# Pressure_sensors.net
KiCad netlist of a schematic drawn in Altium Designer
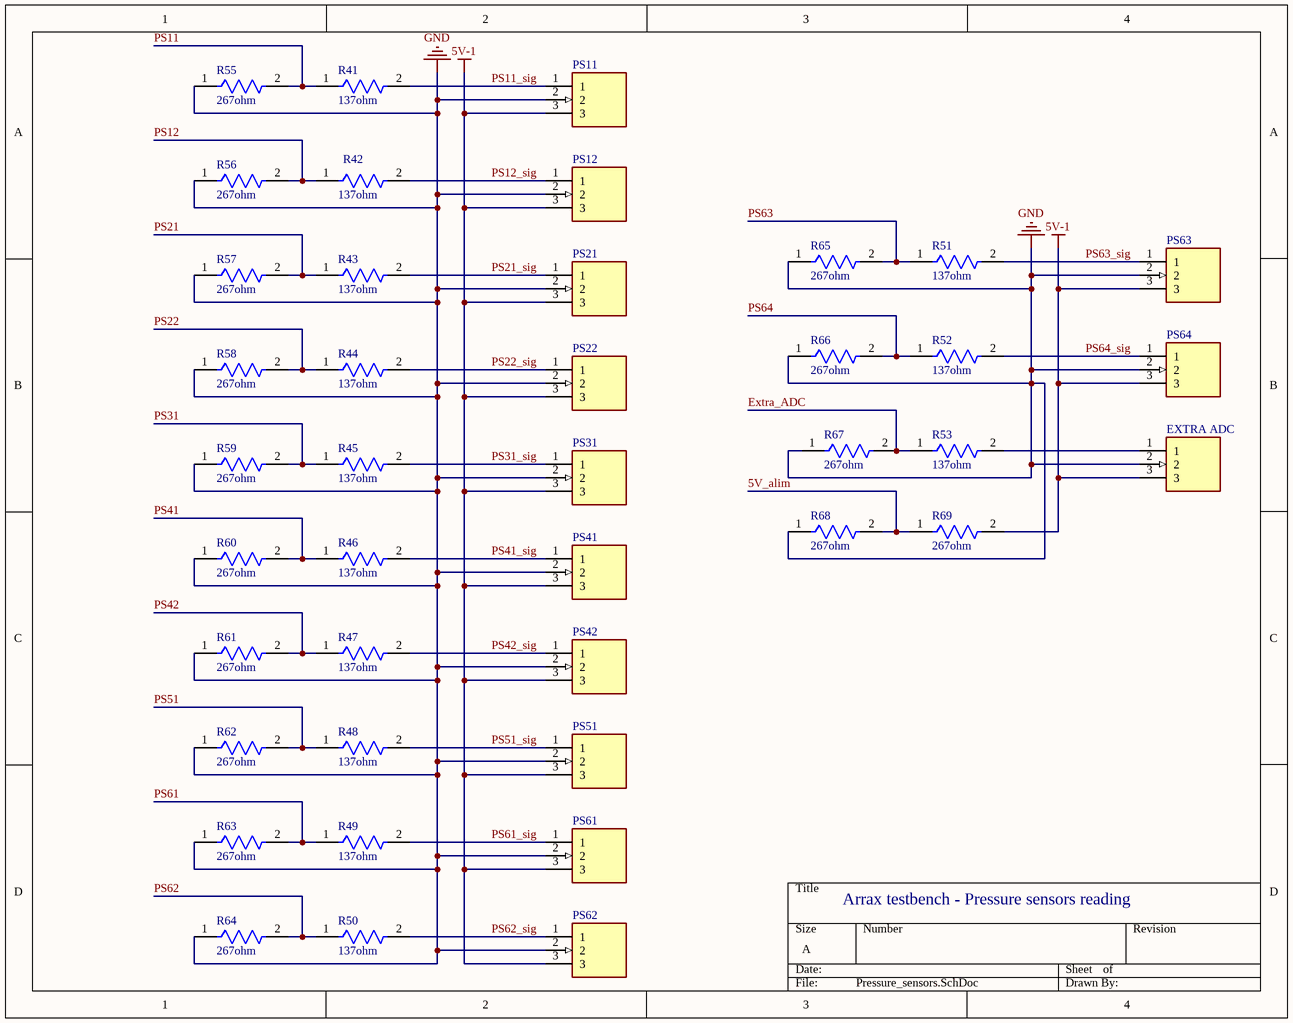
[diagram p0: Pressure_sensors.SchDoc]

(export (version "E")
  (design (tool "Eeschema 10.0.6"))
  (components
    (comp (ref "EXTRA ADC")
      (value "640456-3")
      (footprint "SamacSys:HDRV3W107P0X254_1X3_762X572X1080P")
      (description "Connector")
      (fields (field (name "MOUSER PART NUMBER") "571-6404563"))
      (libsource (lib "*") (part "640456-3"))
    )
    (comp (ref "PS11")
      (value "640456-3")
      (footprint "SamacSys:HDRV3W107P0X254_1X3_762X572X1080P")
      (description "Connector")
      (fields (field (name "MOUSER PART NUMBER") "571-6404563"))
      (libsource (lib "*") (part "640456-3"))
    )
    (comp (ref "PS12")
      (value "640456-3")
      (footprint "SamacSys:HDRV3W107P0X254_1X3_762X572X1080P")
      (description "Connector")
      (fields (field (name "MOUSER PART NUMBER") "571-6404563"))
      (libsource (lib "*") (part "640456-3"))
    )
    (comp (ref "PS21")
      (value "640456-3")
      (footprint "SamacSys:HDRV3W107P0X254_1X3_762X572X1080P")
      (description "Connector")
      (fields (field (name "MOUSER PART NUMBER") "571-6404563"))
      (libsource (lib "*") (part "640456-3"))
    )
    (comp (ref "PS22")
      (value "640456-3")
      (footprint "SamacSys:HDRV3W107P0X254_1X3_762X572X1080P")
      (description "Connector")
      (fields (field (name "MOUSER PART NUMBER") "571-6404563"))
      (libsource (lib "*") (part "640456-3"))
    )
    (comp (ref "PS31")
      (value "640456-3")
      (footprint "SamacSys:HDRV3W107P0X254_1X3_762X572X1080P")
      (description "Connector")
      (fields (field (name "MOUSER PART NUMBER") "571-6404563"))
      (libsource (lib "*") (part "640456-3"))
    )
    (comp (ref "PS41")
      (value "640456-3")
      (footprint "SamacSys:HDRV3W107P0X254_1X3_762X572X1080P")
      (description "Connector")
      (fields (field (name "MOUSER PART NUMBER") "571-6404563"))
      (libsource (lib "*") (part "640456-3"))
    )
    (comp (ref "PS42")
      (value "640456-3")
      (footprint "SamacSys:HDRV3W107P0X254_1X3_762X572X1080P")
      (description "Connector")
      (fields (field (name "MOUSER PART NUMBER") "571-6404563"))
      (libsource (lib "*") (part "640456-3"))
    )
    (comp (ref "PS51")
      (value "640456-3")
      (footprint "SamacSys:HDRV3W107P0X254_1X3_762X572X1080P")
      (description "Connector")
      (fields (field (name "MOUSER PART NUMBER") "571-6404563"))
      (libsource (lib "*") (part "640456-3"))
    )
    (comp (ref "PS61")
      (value "640456-3")
      (footprint "SamacSys:HDRV3W107P0X254_1X3_762X572X1080P")
      (description "Connector")
      (fields (field (name "MOUSER PART NUMBER") "571-6404563"))
      (libsource (lib "*") (part "640456-3"))
    )
    (comp (ref "PS62")
      (value "640456-3")
      (footprint "SamacSys:HDRV3W107P0X254_1X3_762X572X1080P")
      (description "Connector")
      (fields (field (name "MOUSER PART NUMBER") "571-6404563"))
      (libsource (lib "*") (part "640456-3"))
    )
    (comp (ref "PS63")
      (value "640456-3")
      (footprint "SamacSys:HDRV3W107P0X254_1X3_762X572X1080P")
      (description "Connector")
      (fields (field (name "MOUSER PART NUMBER") "571-6404563"))
      (libsource (lib "*") (part "640456-3"))
    )
    (comp (ref "PS64")
      (value "640456-3")
      (footprint "SamacSys:HDRV3W107P0X254_1X3_762X572X1080P")
      (description "Connector")
      (fields (field (name "MOUSER PART NUMBER") "571-6404563"))
      (libsource (lib "*") (part "640456-3"))
    )
    (comp (ref "R41")
      (value "137ohm")
      (footprint "FP-RP73P-2A-MFG")
      (description "RP73P 0805 137Ω 0.25W 25ppm/°C 0.10% 150V")
      (fields
        (field (name "MANUFACTURER PART NUMBER") "RP73PF2A137RBTDF")
        (field (name "MANUFACTURER") "TE Connectivity")
      )
      (libsource (lib "Altium Content Vault") (part "1029c3af85768c4190bb7ad29bc67b5"))
    )
    (comp (ref "R42")
      (value "137ohm")
      (footprint "FP-RP73P-2A-MFG")
      (description "RP73P 0805 137Ω 0.25W 25ppm/°C 0.10% 150V")
      (fields
        (field (name "MANUFACTURER PART NUMBER") "RP73PF2A137RBTDF")
        (field (name "MANUFACTURER") "TE Connectivity")
      )
      (libsource (lib "Altium Content Vault") (part "1029c3af85768c4190bb7ad29bc67b5"))
    )
    (comp (ref "R43")
      (value "137ohm")
      (footprint "FP-RP73P-2A-MFG")
      (description "RP73P 0805 137Ω 0.25W 25ppm/°C 0.10% 150V")
      (fields
        (field (name "MANUFACTURER PART NUMBER") "RP73PF2A137RBTDF")
        (field (name "MANUFACTURER") "TE Connectivity")
      )
      (libsource (lib "Altium Content Vault") (part "1029c3af85768c4190bb7ad29bc67b5"))
    )
    (comp (ref "R44")
      (value "137ohm")
      (footprint "FP-RP73P-2A-MFG")
      (description "RP73P 0805 137Ω 0.25W 25ppm/°C 0.10% 150V")
      (fields
        (field (name "MANUFACTURER PART NUMBER") "RP73PF2A137RBTDF")
        (field (name "MANUFACTURER") "TE Connectivity")
      )
      (libsource (lib "Altium Content Vault") (part "1029c3af85768c4190bb7ad29bc67b5"))
    )
    (comp (ref "R45")
      (value "137ohm")
      (footprint "FP-RP73P-2A-MFG")
      (description "RP73P 0805 137Ω 0.25W 25ppm/°C 0.10% 150V")
      (fields
        (field (name "MANUFACTURER PART NUMBER") "RP73PF2A137RBTDF")
        (field (name "MANUFACTURER") "TE Connectivity")
      )
      (libsource (lib "Altium Content Vault") (part "1029c3af85768c4190bb7ad29bc67b5"))
    )
    (comp (ref "R46")
      (value "137ohm")
      (footprint "FP-RP73P-2A-MFG")
      (description "RP73P 0805 137Ω 0.25W 25ppm/°C 0.10% 150V")
      (fields
        (field (name "MANUFACTURER PART NUMBER") "RP73PF2A137RBTDF")
        (field (name "MANUFACTURER") "TE Connectivity")
      )
      (libsource (lib "Altium Content Vault") (part "1029c3af85768c4190bb7ad29bc67b5"))
    )
    (comp (ref "R47")
      (value "137ohm")
      (footprint "FP-RP73P-2A-MFG")
      (description "RP73P 0805 137Ω 0.25W 25ppm/°C 0.10% 150V")
      (fields
        (field (name "MANUFACTURER PART NUMBER") "RP73PF2A137RBTDF")
        (field (name "MANUFACTURER") "TE Connectivity")
      )
      (libsource (lib "Altium Content Vault") (part "1029c3af85768c4190bb7ad29bc67b5"))
    )
    (comp (ref "R48")
      (value "137ohm")
      (footprint "FP-RP73P-2A-MFG")
      (description "RP73P 0805 137Ω 0.25W 25ppm/°C 0.10% 150V")
      (fields
        (field (name "MANUFACTURER PART NUMBER") "RP73PF2A137RBTDF")
        (field (name "MANUFACTURER") "TE Connectivity")
      )
      (libsource (lib "Altium Content Vault") (part "1029c3af85768c4190bb7ad29bc67b5"))
    )
    (comp (ref "R49")
      (value "137ohm")
      (footprint "FP-RP73P-2A-MFG")
      (description "RP73P 0805 137Ω 0.25W 25ppm/°C 0.10% 150V")
      (fields
        (field (name "MANUFACTURER PART NUMBER") "RP73PF2A137RBTDF")
        (field (name "MANUFACTURER") "TE Connectivity")
      )
      (libsource (lib "Altium Content Vault") (part "1029c3af85768c4190bb7ad29bc67b5"))
    )
    (comp (ref "R50")
      (value "137ohm")
      (footprint "FP-RP73P-2A-MFG")
      (description "RP73P 0805 137Ω 0.25W 25ppm/°C 0.10% 150V")
      (fields
        (field (name "MANUFACTURER PART NUMBER") "RP73PF2A137RBTDF")
        (field (name "MANUFACTURER") "TE Connectivity")
      )
      (libsource (lib "Altium Content Vault") (part "1029c3af85768c4190bb7ad29bc67b5"))
    )
    (comp (ref "R51")
      (value "137ohm")
      (footprint "FP-RP73P-2A-MFG")
      (description "RP73P 0805 137Ω 0.25W 25ppm/°C 0.10% 150V")
      (fields
        (field (name "MANUFACTURER PART NUMBER") "RP73PF2A137RBTDF")
        (field (name "MANUFACTURER") "TE Connectivity")
      )
      (libsource (lib "Altium Content Vault") (part "1029c3af85768c4190bb7ad29bc67b5"))
    )
    (comp (ref "R52")
      (value "137ohm")
      (footprint "FP-RP73P-2A-MFG")
      (description "RP73P 0805 137Ω 0.25W 25ppm/°C 0.10% 150V")
      (fields
        (field (name "MANUFACTURER PART NUMBER") "RP73PF2A137RBTDF")
        (field (name "MANUFACTURER") "TE Connectivity")
      )
      (libsource (lib "Altium Content Vault") (part "1029c3af85768c4190bb7ad29bc67b5"))
    )
    (comp (ref "R53")
      (value "137ohm")
      (footprint "FP-RP73P-2A-MFG")
      (description "RP73P 0805 137Ω 0.25W 25ppm/°C 0.10% 150V")
      (fields
        (field (name "MANUFACTURER PART NUMBER") "RP73PF2A137RBTDF")
        (field (name "MANUFACTURER") "TE Connectivity")
      )
      (libsource (lib "Altium Content Vault") (part "1029c3af85768c4190bb7ad29bc67b5"))
    )
    (comp (ref "R55")
      (value "267ohm")
      (footprint "FP-RP73P-2A-MFG")
      (description "RP73P 0805 267Ω 0.25W 25ppm/°C 0.10% 150V")
      (fields (field (name "TOLERANCE") "0.001") (field (name "MANUFACTURER PART NUMBER") "RP73PF2A267RBTDF"))
      (libsource (lib "Altium Content Vault") (part "1029c3af85768c4190bb7ad29bc67b5"))
    )
    (comp (ref "R56")
      (value "267ohm")
      (footprint "FP-RP73P-2A-MFG")
      (description "RP73P 0805 267Ω 0.25W 25ppm/°C 0.10% 150V")
      (fields (field (name "TOLERANCE") "0.001") (field (name "MANUFACTURER PART NUMBER") "RP73PF2A267RBTDF"))
      (libsource (lib "Altium Content Vault") (part "1029c3af85768c4190bb7ad29bc67b5"))
    )
    (comp (ref "R57")
      (value "267ohm")
      (footprint "FP-RP73P-2A-MFG")
      (description "RP73P 0805 267Ω 0.25W 25ppm/°C 0.10% 150V")
      (fields (field (name "TOLERANCE") "0.001") (field (name "MANUFACTURER PART NUMBER") "RP73PF2A267RBTDF"))
      (libsource (lib "Altium Content Vault") (part "1029c3af85768c4190bb7ad29bc67b5"))
    )
    (comp (ref "R58")
      (value "267ohm")
      (footprint "FP-RP73P-2A-MFG")
      (description "RP73P 0805 267Ω 0.25W 25ppm/°C 0.10% 150V")
      (fields (field (name "TOLERANCE") "0.001") (field (name "MANUFACTURER PART NUMBER") "RP73PF2A267RBTDF"))
      (libsource (lib "Altium Content Vault") (part "1029c3af85768c4190bb7ad29bc67b5"))
    )
    (comp (ref "R59")
      (value "267ohm")
      (footprint "FP-RP73P-2A-MFG")
      (description "RP73P 0805 267Ω 0.25W 25ppm/°C 0.10% 150V")
      (fields (field (name "TOLERANCE") "0.001") (field (name "MANUFACTURER PART NUMBER") "RP73PF2A267RBTDF"))
      (libsource (lib "Altium Content Vault") (part "1029c3af85768c4190bb7ad29bc67b5"))
    )
    (comp (ref "R60")
      (value "267ohm")
      (footprint "FP-RP73P-2A-MFG")
      (description "RP73P 0805 267Ω 0.25W 25ppm/°C 0.10% 150V")
      (fields (field (name "TOLERANCE") "0.001") (field (name "MANUFACTURER PART NUMBER") "RP73PF2A267RBTDF"))
      (libsource (lib "Altium Content Vault") (part "1029c3af85768c4190bb7ad29bc67b5"))
    )
    (comp (ref "R61")
      (value "267ohm")
      (footprint "FP-RP73P-2A-MFG")
      (description "RP73P 0805 267Ω 0.25W 25ppm/°C 0.10% 150V")
      (fields (field (name "TOLERANCE") "0.001") (field (name "MANUFACTURER PART NUMBER") "RP73PF2A267RBTDF"))
      (libsource (lib "Altium Content Vault") (part "1029c3af85768c4190bb7ad29bc67b5"))
    )
    (comp (ref "R62")
      (value "267ohm")
      (footprint "FP-RP73P-2A-MFG")
      (description "RP73P 0805 267Ω 0.25W 25ppm/°C 0.10% 150V")
      (fields (field (name "TOLERANCE") "0.001") (field (name "MANUFACTURER PART NUMBER") "RP73PF2A267RBTDF"))
      (libsource (lib "Altium Content Vault") (part "1029c3af85768c4190bb7ad29bc67b5"))
    )
    (comp (ref "R63")
      (value "267ohm")
      (footprint "FP-RP73P-2A-MFG")
      (description "RP73P 0805 267Ω 0.25W 25ppm/°C 0.10% 150V")
      (fields (field (name "TOLERANCE") "0.001") (field (name "MANUFACTURER PART NUMBER") "RP73PF2A267RBTDF"))
      (libsource (lib "Altium Content Vault") (part "1029c3af85768c4190bb7ad29bc67b5"))
    )
    (comp (ref "R64")
      (value "267ohm")
      (footprint "FP-RP73P-2A-MFG")
      (description "RP73P 0805 267Ω 0.25W 25ppm/°C 0.10% 150V")
      (fields (field (name "TOLERANCE") "0.001") (field (name "MANUFACTURER PART NUMBER") "RP73PF2A267RBTDF"))
      (libsource (lib "Altium Content Vault") (part "1029c3af85768c4190bb7ad29bc67b5"))
    )
    (comp (ref "R65")
      (value "267ohm")
      (footprint "FP-RP73P-2A-MFG")
      (description "RP73P 0805 267Ω 0.25W 25ppm/°C 0.10% 150V")
      (fields (field (name "TOLERANCE") "0.001") (field (name "MANUFACTURER PART NUMBER") "RP73PF2A267RBTDF"))
      (libsource (lib "Altium Content Vault") (part "1029c3af85768c4190bb7ad29bc67b5"))
    )
    (comp (ref "R66")
      (value "267ohm")
      (footprint "FP-RP73P-2A-MFG")
      (description "RP73P 0805 267Ω 0.25W 25ppm/°C 0.10% 150V")
      (fields (field (name "TOLERANCE") "0.001") (field (name "MANUFACTURER PART NUMBER") "RP73PF2A267RBTDF"))
      (libsource (lib "Altium Content Vault") (part "1029c3af85768c4190bb7ad29bc67b5"))
    )
    (comp (ref "R67")
      (value "267ohm")
      (footprint "FP-RP73P-2A-MFG")
      (description "RP73P 0805 267Ω 0.25W 25ppm/°C 0.10% 150V")
      (fields (field (name "TOLERANCE") "0.001") (field (name "MANUFACTURER PART NUMBER") "RP73PF2A267RBTDF"))
      (libsource (lib "Altium Content Vault") (part "1029c3af85768c4190bb7ad29bc67b5"))
    )
    (comp (ref "R68")
      (value "267ohm")
      (footprint "FP-RP73P-2A-MFG")
      (description "RP73P 0805 267Ω 0.25W 25ppm/°C 0.10% 150V")
      (fields (field (name "TOLERANCE") "0.001") (field (name "MANUFACTURER PART NUMBER") "RP73PF2A267RBTDF"))
      (libsource (lib "Altium Content Vault") (part "1029c3af85768c4190bb7ad29bc67b5"))
    )
    (comp (ref "R69")
      (value "267ohm")
      (footprint "FP-RP73P-2A-MFG")
      (description "RP73P 0805 267Ω 0.25W 25ppm/°C 0.10% 150V")
      (fields (field (name "TOLERANCE") "0.001") (field (name "MANUFACTURER PART NUMBER") "RP73PF2A267RBTDF"))
      (libsource (lib "Altium Content Vault") (part "1029c3af85768c4190bb7ad29bc67b5"))
    )
  )
  (nets
    (net (code "1") (name "/5V_alim") (class "Default")
      (node (ref "R68") (pin "2") (pinfunction "2_2") (pintype "passive"))
      (node (ref "R69") (pin "1") (pinfunction "1_1") (pintype "passive"))
    )
    (net (code "2") (name "/Extra_ADC") (class "Default")
      (node (ref "R53") (pin "1") (pinfunction "1_1") (pintype "passive"))
      (node (ref "R67") (pin "2") (pinfunction "2_2") (pintype "passive"))
    )
    (net (code "3") (name "/PS11") (class "Default")
      (node (ref "R41") (pin "1") (pinfunction "1_1") (pintype "passive"))
      (node (ref "R55") (pin "2") (pinfunction "2_2") (pintype "passive"))
    )
    (net (code "4") (name "/PS11_sig") (class "Default")
      (node (ref "PS11") (pin "1") (pinfunction "1_1") (pintype "passive"))
      (node (ref "R41") (pin "2") (pinfunction "2_2") (pintype "passive"))
    )
    (net (code "5") (name "/PS12") (class "Default")
      (node (ref "R42") (pin "1") (pinfunction "1_1") (pintype "passive"))
      (node (ref "R56") (pin "2") (pinfunction "2_2") (pintype "passive"))
    )
    (net (code "6") (name "/PS12_sig") (class "Default")
      (node (ref "PS12") (pin "1") (pinfunction "1_1") (pintype "passive"))
      (node (ref "R42") (pin "2") (pinfunction "2_2") (pintype "passive"))
    )
    (net (code "7") (name "/PS21") (class "Default")
      (node (ref "R43") (pin "1") (pinfunction "1_1") (pintype "passive"))
      (node (ref "R57") (pin "2") (pinfunction "2_2") (pintype "passive"))
    )
    (net (code "8") (name "/PS21_sig") (class "Default")
      (node (ref "PS21") (pin "1") (pinfunction "1_1") (pintype "passive"))
      (node (ref "R43") (pin "2") (pinfunction "2_2") (pintype "passive"))
    )
    (net (code "9") (name "/PS22") (class "Default")
      (node (ref "R44") (pin "1") (pinfunction "1_1") (pintype "passive"))
      (node (ref "R58") (pin "2") (pinfunction "2_2") (pintype "passive"))
    )
    (net (code "10") (name "/PS22_sig") (class "Default")
      (node (ref "PS22") (pin "1") (pinfunction "1_1") (pintype "passive"))
      (node (ref "R44") (pin "2") (pinfunction "2_2") (pintype "passive"))
    )
    (net (code "11") (name "/PS31") (class "Default")
      (node (ref "R45") (pin "1") (pinfunction "1_1") (pintype "passive"))
      (node (ref "R59") (pin "2") (pinfunction "2_2") (pintype "passive"))
    )
    (net (code "12") (name "/PS31_sig") (class "Default")
      (node (ref "PS31") (pin "1") (pinfunction "1_1") (pintype "passive"))
      (node (ref "R45") (pin "2") (pinfunction "2_2") (pintype "passive"))
    )
    (net (code "13") (name "/PS41") (class "Default")
      (node (ref "R46") (pin "1") (pinfunction "1_1") (pintype "passive"))
      (node (ref "R60") (pin "2") (pinfunction "2_2") (pintype "passive"))
    )
    (net (code "14") (name "/PS41_sig") (class "Default")
      (node (ref "PS41") (pin "1") (pinfunction "1_1") (pintype "passive"))
      (node (ref "R46") (pin "2") (pinfunction "2_2") (pintype "passive"))
    )
    (net (code "15") (name "/PS42") (class "Default")
      (node (ref "R47") (pin "1") (pinfunction "1_1") (pintype "passive"))
      (node (ref "R61") (pin "2") (pinfunction "2_2") (pintype "passive"))
    )
    (net (code "16") (name "/PS42_sig") (class "Default")
      (node (ref "PS42") (pin "1") (pinfunction "1_1") (pintype "passive"))
      (node (ref "R47") (pin "2") (pinfunction "2_2") (pintype "passive"))
    )
    (net (code "17") (name "/PS51") (class "Default")
      (node (ref "R48") (pin "1") (pinfunction "1_1") (pintype "passive"))
      (node (ref "R62") (pin "2") (pinfunction "2_2") (pintype "passive"))
    )
    (net (code "18") (name "/PS51_sig") (class "Default")
      (node (ref "PS51") (pin "1") (pinfunction "1_1") (pintype "passive"))
      (node (ref "R48") (pin "2") (pinfunction "2_2") (pintype "passive"))
    )
    (net (code "19") (name "/PS61") (class "Default")
      (node (ref "R49") (pin "1") (pinfunction "1_1") (pintype "passive"))
      (node (ref "R63") (pin "2") (pinfunction "2_2") (pintype "passive"))
    )
    (net (code "20") (name "/PS61_sig") (class "Default")
      (node (ref "PS61") (pin "1") (pinfunction "1_1") (pintype "passive"))
      (node (ref "R49") (pin "2") (pinfunction "2_2") (pintype "passive"))
    )
    (net (code "21") (name "/PS62") (class "Default")
      (node (ref "R50") (pin "1") (pinfunction "1_1") (pintype "passive"))
      (node (ref "R64") (pin "2") (pinfunction "2_2") (pintype "passive"))
    )
    (net (code "22") (name "/PS62_sig") (class "Default")
      (node (ref "PS62") (pin "1") (pinfunction "1_1") (pintype "passive"))
      (node (ref "R50") (pin "2") (pinfunction "2_2") (pintype "passive"))
    )
    (net (code "23") (name "/PS63") (class "Default")
      (node (ref "R51") (pin "1") (pinfunction "1_1") (pintype "passive"))
      (node (ref "R65") (pin "2") (pinfunction "2_2") (pintype "passive"))
    )
    (net (code "24") (name "/PS63_sig") (class "Default")
      (node (ref "PS63") (pin "1") (pinfunction "1_1") (pintype "passive"))
      (node (ref "R51") (pin "2") (pinfunction "2_2") (pintype "passive"))
    )
    (net (code "25") (name "/PS64") (class "Default")
      (node (ref "R52") (pin "1") (pinfunction "1_1") (pintype "passive"))
      (node (ref "R66") (pin "2") (pinfunction "2_2") (pintype "passive"))
    )
    (net (code "26") (name "/PS64_sig") (class "Default")
      (node (ref "PS64") (pin "1") (pinfunction "1_1") (pintype "passive"))
      (node (ref "R52") (pin "2") (pinfunction "2_2") (pintype "passive"))
    )
    (net (code "27") (name "5V-1") (class "Default")
      (node (ref "EXTRA ADC") (pin "3") (pinfunction "3_3") (pintype "passive"))
      (node (ref "PS11") (pin "3") (pinfunction "3_3") (pintype "passive"))
      (node (ref "PS12") (pin "3") (pinfunction "3_3") (pintype "passive"))
      (node (ref "PS21") (pin "3") (pinfunction "3_3") (pintype "passive"))
      (node (ref "PS22") (pin "3") (pinfunction "3_3") (pintype "passive"))
      (node (ref "PS31") (pin "3") (pinfunction "3_3") (pintype "passive"))
      (node (ref "PS41") (pin "3") (pinfunction "3_3") (pintype "passive"))
      (node (ref "PS42") (pin "3") (pinfunction "3_3") (pintype "passive"))
      (node (ref "PS51") (pin "3") (pinfunction "3_3") (pintype "passive"))
      (node (ref "PS61") (pin "3") (pinfunction "3_3") (pintype "passive"))
      (node (ref "PS62") (pin "3") (pinfunction "3_3") (pintype "passive"))
      (node (ref "PS63") (pin "3") (pinfunction "3_3") (pintype "passive"))
      (node (ref "PS64") (pin "3") (pinfunction "3_3") (pintype "passive"))
      (node (ref "R69") (pin "2") (pinfunction "2_2") (pintype "passive"))
    )
    (net (code "28") (name "GND") (class "Default")
      (node (ref "EXTRA ADC") (pin "2") (pinfunction "2_2") (pintype "input"))
      (node (ref "PS11") (pin "2") (pinfunction "2_2") (pintype "input"))
      (node (ref "PS12") (pin "2") (pinfunction "2_2") (pintype "input"))
      (node (ref "PS21") (pin "2") (pinfunction "2_2") (pintype "input"))
      (node (ref "PS22") (pin "2") (pinfunction "2_2") (pintype "input"))
      (node (ref "PS31") (pin "2") (pinfunction "2_2") (pintype "input"))
      (node (ref "PS41") (pin "2") (pinfunction "2_2") (pintype "input"))
      (node (ref "PS42") (pin "2") (pinfunction "2_2") (pintype "input"))
      (node (ref "PS51") (pin "2") (pinfunction "2_2") (pintype "input"))
      (node (ref "PS61") (pin "2") (pinfunction "2_2") (pintype "input"))
      (node (ref "PS62") (pin "2") (pinfunction "2_2") (pintype "input"))
      (node (ref "PS63") (pin "2") (pinfunction "2_2") (pintype "input"))
      (node (ref "PS64") (pin "2") (pinfunction "2_2") (pintype "input"))
      (node (ref "R55") (pin "1") (pinfunction "1_1") (pintype "passive"))
      (node (ref "R56") (pin "1") (pinfunction "1_1") (pintype "passive"))
      (node (ref "R57") (pin "1") (pinfunction "1_1") (pintype "passive"))
      (node (ref "R58") (pin "1") (pinfunction "1_1") (pintype "passive"))
      (node (ref "R59") (pin "1") (pinfunction "1_1") (pintype "passive"))
      (node (ref "R60") (pin "1") (pinfunction "1_1") (pintype "passive"))
      (node (ref "R61") (pin "1") (pinfunction "1_1") (pintype "passive"))
      (node (ref "R62") (pin "1") (pinfunction "1_1") (pintype "passive"))
      (node (ref "R63") (pin "1") (pinfunction "1_1") (pintype "passive"))
      (node (ref "R64") (pin "1") (pinfunction "1_1") (pintype "passive"))
      (node (ref "R65") (pin "1") (pinfunction "1_1") (pintype "passive"))
      (node (ref "R66") (pin "1") (pinfunction "1_1") (pintype "passive"))
      (node (ref "R67") (pin "1") (pinfunction "1_1") (pintype "passive"))
      (node (ref "R68") (pin "1") (pinfunction "1_1") (pintype "passive"))
    )
    (net (code "29") (name "Net-(EXTRA ADC-Pad1)") (class "Default")
      (node (ref "EXTRA ADC") (pin "1") (pinfunction "1_1") (pintype "passive"))
      (node (ref "R53") (pin "2") (pinfunction "2_2") (pintype "passive"))
    )
  )
)
